# 04_-_MCU_STM32.net
KiCad netlist of a schematic drawn in Altium Designer
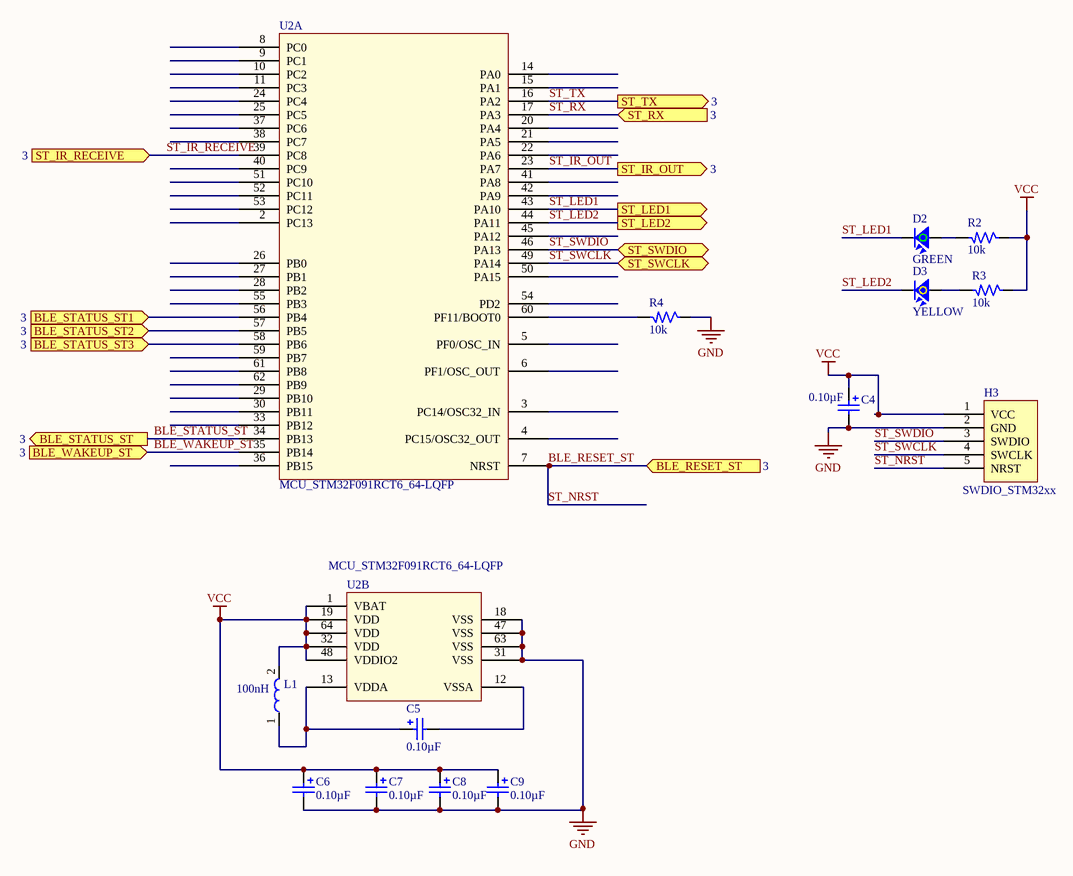
[diagram p0: [04] - MCU STM32.SchDoc]

(export (version "E")
  (design (tool "Eeschema 10.0.6"))
  (components
    (comp (ref "C4")
      (value "C_104_0603_CERAMIC_16V")
      (footprint "CAP_SMD0603")
      (description "CAP CER 0.1UF 16V X7R 0603")
      (fields
        (field (name "MANUFACTURER") "Murata Electronics North America")
        (field (name "MANUFACTURER PART NUMBER") "GRM188R71C104KA01D")
        (field (name "CAPACITANCE") "0.10µF")
      )
      (libsource (lib "ALTIUM_LIB") (part "C_104_0603_CERAMIC_16V"))
    )
    (comp (ref "C5")
      (value "C_104_0603_CERAMIC_16V")
      (footprint "CAP_SMD0603")
      (description "CAP CER 0.1UF 16V X7R 0603")
      (fields
        (field (name "MANUFACTURER") "Murata Electronics North America")
        (field (name "MANUFACTURER PART NUMBER") "GRM188R71C104KA01D")
        (field (name "CAPACITANCE") "0.10µF")
      )
      (libsource (lib "ALTIUM_LIB") (part "C_104_0603_CERAMIC_16V"))
    )
    (comp (ref "C6")
      (value "C_104_0603_CERAMIC_16V")
      (footprint "CAP_SMD0603")
      (description "CAP CER 0.1UF 16V X7R 0603")
      (fields
        (field (name "MANUFACTURER") "Murata Electronics North America")
        (field (name "MANUFACTURER PART NUMBER") "GRM188R71C104KA01D")
        (field (name "CAPACITANCE") "0.10µF")
      )
      (libsource (lib "ALTIUM_LIB") (part "C_104_0603_CERAMIC_16V"))
    )
    (comp (ref "C7")
      (value "C_104_0603_CERAMIC_16V")
      (footprint "CAP_SMD0603")
      (description "CAP CER 0.1UF 16V X7R 0603")
      (fields
        (field (name "MANUFACTURER") "Murata Electronics North America")
        (field (name "MANUFACTURER PART NUMBER") "GRM188R71C104KA01D")
        (field (name "CAPACITANCE") "0.10µF")
      )
      (libsource (lib "ALTIUM_LIB") (part "C_104_0603_CERAMIC_16V"))
    )
    (comp (ref "C8")
      (value "C_104_0603_CERAMIC_16V")
      (footprint "CAP_SMD0603")
      (description "CAP CER 0.1UF 16V X7R 0603")
      (fields
        (field (name "MANUFACTURER") "Murata Electronics North America")
        (field (name "MANUFACTURER PART NUMBER") "GRM188R71C104KA01D")
        (field (name "CAPACITANCE") "0.10µF")
      )
      (libsource (lib "ALTIUM_LIB") (part "C_104_0603_CERAMIC_16V"))
    )
    (comp (ref "C9")
      (value "C_104_0603_CERAMIC_16V")
      (footprint "CAP_SMD0603")
      (description "CAP CER 0.1UF 16V X7R 0603")
      (fields
        (field (name "MANUFACTURER") "Murata Electronics North America")
        (field (name "MANUFACTURER PART NUMBER") "GRM188R71C104KA01D")
        (field (name "CAPACITANCE") "0.10µF")
      )
      (libsource (lib "ALTIUM_LIB") (part "C_104_0603_CERAMIC_16V"))
    )
    (comp (ref "D2")
      (value "GREEN")
      (footprint "LED_GREEN_SMD0603")
      (description "LED GREEN CLEAR 0603 SMD")
      (fields
        (field (name "MANUFACTURER") "Lite-On Inc.")
        (field (name "MANUFACTURER PART NUMBER") "LTST-C191KGKT")
      )
      (libsource (lib "ALTIUM_LIB") (part "LED2_GREEN_0603_2V"))
    )
    (comp (ref "D3")
      (value "YELLOW")
      (footprint "LED_YELLOW_SMD0603")
      (description "LED YELLOW CLEAR 0603 SMD")
      (fields
        (field (name "MANUFACTURER") "Lite-On Inc.")
        (field (name "MANUFACTURER PART NUMBER") "LTST-C191KSKT")
      )
      (libsource (lib "ALTIUM_LIB") (part "LED2_YELLOW_0603_2.1V"))
    )
    (comp (ref "H3")
      (value "SWDIO_STM32xx")
      (footprint "HEADER5_ISP_STM32F0xx_SUR1.27 - duplicate")
      (description "CONN HEADER 5 POS 2.54")
      (fields
        (field (name "MANUFACTURER") "Wurth Electronics Inc")
        (field (name "MANUFACTURER PART NUMBER") "61300511121")
      )
      (libsource (lib "ALTIUM_LIB") (part "HEADER5_ISP_STM32xx_HOLE_2.54"))
    )
    (comp (ref "L1")
      (value "CHOKE_100NH_SMD0805")
      (footprint "CHOKE_SMD0805")
      (description "FIXED IND 100NH 300MA 900 MOHM")
      (fields
        (field (name "MANUFACTURER") "Jaro Components Inc.")
        (field (name "MANUFACTURER PART NUMBER") "HFI-201209-R10J")
        (field (name "INDUCTANCE") "100nH")
      )
      (libsource (lib "SchematicLib") (part "CHOKE_100NH_SMD0805"))
    )
    (comp (ref "R2")
      (value "R_10K_SMD0603_1%_1/10W")
      (footprint "RES_SMD0603")
      (description "RES SMD 10K OHM 1% 1/10W 0603")
      (fields
        (field (name "MANUFACTURER") "Yageo")
        (field (name "MANUFACTURER PART NUMBER") "RC0603FR-0710KL")
        (field (name "RESISTANCE (OHMS)") "10k")
      )
      (libsource (lib "ALTIUM_LIB") (part "R_10K_SMD0603_1%_1/10W"))
    )
    (comp (ref "R3")
      (value "R_10K_SMD0603_1%_1/10W")
      (footprint "RES_SMD0603")
      (description "RES SMD 10K OHM 1% 1/10W 0603")
      (fields
        (field (name "MANUFACTURER") "Yageo")
        (field (name "MANUFACTURER PART NUMBER") "RC0603FR-0710KL")
        (field (name "RESISTANCE (OHMS)") "10k")
      )
      (libsource (lib "ALTIUM_LIB") (part "R_10K_SMD0603_1%_1/10W"))
    )
    (comp (ref "R4")
      (value "R_10K_SMD0603_1%_1/10W")
      (footprint "RES_SMD0603")
      (description "RES SMD 10K OHM 1% 1/10W 0603")
      (fields
        (field (name "MANUFACTURER") "Yageo")
        (field (name "MANUFACTURER PART NUMBER") "RC0603FR-0710KL")
        (field (name "RESISTANCE (OHMS)") "10k")
      )
      (libsource (lib "ALTIUM_LIB") (part "R_10K_SMD0603_1%_1/10W"))
    )
    (comp (ref "U2")
      (value "MCU_STM32F091RCT6_64-LQFP")
      (footprint "MCU_STM32F091RCT6_LQFP64")
      (description "IC MCU 32BIT 256KB FLASH 64LQFP")
      (fields
        (field (name "MANUFACTURER") "STMicroelectronics")
        (field (name "MANUFACTURER PART NUMBER") "STM32F091RCT6")
      )
      (libsource (lib "ALTIUM_LIB") (part "MCU_STM32F091RCT6_64-LQFP"))
    )
  )
  (nets
    (net (code "1") (name "/BLE_RESET_ST") (class "Default")
      (node (ref "H3") (pin "5") (pinfunction "NRST_5") (pintype "passive"))
      (node (ref "U2") (pin "7") (pinfunction "NRST_7") (pintype "passive"))
    )
    (net (code "2") (name "/BLE_STATUS_ST") (class "Default")
      (node (ref "U2") (pin "34") (pinfunction "PB13_34") (pintype "passive"))
    )
    (net (code "3") (name "/BLE_STATUS_ST1") (class "Default")
      (node (ref "U2") (pin "56") (pinfunction "PB4_56") (pintype "passive"))
    )
    (net (code "4") (name "/BLE_STATUS_ST2") (class "Default")
      (node (ref "U2") (pin "57") (pinfunction "PB5_57") (pintype "passive"))
    )
    (net (code "5") (name "/BLE_STATUS_ST3") (class "Default")
      (node (ref "U2") (pin "58") (pinfunction "PB6_58") (pintype "passive"))
    )
    (net (code "6") (name "/BLE_WAKEUP_ST") (class "Default")
      (node (ref "U2") (pin "35") (pinfunction "PB14_35") (pintype "passive"))
    )
    (net (code "7") (name "/ST_IR_OUT") (class "Default")
      (node (ref "U2") (pin "23") (pinfunction "PA7_23") (pintype "passive"))
    )
    (net (code "8") (name "/ST_IR_RECEIVE") (class "Default")
      (node (ref "U2") (pin "39") (pinfunction "PC8_39") (pintype "passive"))
    )
    (net (code "9") (name "/ST_LED1") (class "Default")
      (node (ref "D2") (pin "2") (pinfunction "2_2") (pintype "passive"))
      (node (ref "U2") (pin "43") (pinfunction "PA10_43") (pintype "passive"))
    )
    (net (code "10") (name "/ST_LED2") (class "Default")
      (node (ref "D3") (pin "2") (pinfunction "2_2") (pintype "passive"))
      (node (ref "U2") (pin "44") (pinfunction "PA11_44") (pintype "passive"))
    )
    (net (code "11") (name "/ST_RX") (class "Default")
      (node (ref "U2") (pin "17") (pinfunction "PA3_17") (pintype "passive"))
    )
    (net (code "12") (name "/ST_SWCLK") (class "Default")
      (node (ref "H3") (pin "4") (pinfunction "SWCLK_4") (pintype "passive"))
      (node (ref "U2") (pin "49") (pinfunction "PA14_49") (pintype "passive"))
    )
    (net (code "13") (name "/ST_SWDIO") (class "Default")
      (node (ref "H3") (pin "3") (pinfunction "SWDIO_3") (pintype "passive"))
      (node (ref "U2") (pin "46") (pinfunction "PA13_46") (pintype "passive"))
    )
    (net (code "14") (name "/ST_TX") (class "Default")
      (node (ref "U2") (pin "16") (pinfunction "PA2_16") (pintype "passive"))
    )
    (net (code "15") (name "GND") (class "Default")
      (node (ref "C4") (pin "2") (pinfunction "2_2") (pintype "passive"))
      (node (ref "C6") (pin "2") (pinfunction "2_2") (pintype "passive"))
      (node (ref "C7") (pin "2") (pinfunction "2_2") (pintype "passive"))
      (node (ref "C8") (pin "2") (pinfunction "2_2") (pintype "passive"))
      (node (ref "C9") (pin "2") (pinfunction "2_2") (pintype "passive"))
      (node (ref "H3") (pin "2") (pinfunction "GND_2") (pintype "passive"))
      (node (ref "R4") (pin "1") (pinfunction "1_1") (pintype "passive"))
      (node (ref "U2") (pin "18") (pinfunction "VSS_18") (pintype "passive"))
      (node (ref "U2") (pin "31") (pinfunction "VSS_31") (pintype "passive"))
      (node (ref "U2") (pin "47") (pinfunction "VSS_47") (pintype "passive"))
      (node (ref "U2") (pin "63") (pinfunction "VSS_63") (pintype "passive"))
    )
    (net (code "16") (name "Net-(D2-Pad1)") (class "Default")
      (node (ref "D2") (pin "1") (pinfunction "1_1") (pintype "passive"))
      (node (ref "R2") (pin "2") (pinfunction "2_2") (pintype "passive"))
    )
    (net (code "17") (name "Net-(D3-Pad1)") (class "Default")
      (node (ref "D3") (pin "1") (pinfunction "1_1") (pintype "passive"))
      (node (ref "R3") (pin "2") (pinfunction "2_2") (pintype "passive"))
    )
    (net (code "18") (name "Net-(U2A-PF11{slash}BOOT0)") (class "Default")
      (node (ref "R4") (pin "2") (pinfunction "2_2") (pintype "passive"))
      (node (ref "U2") (pin "60") (pinfunction "PF11/BOOT0_60") (pintype "passive"))
    )
    (net (code "19") (name "Net-(U2B-VDDA)") (class "Default")
      (node (ref "C5") (pin "1") (pinfunction "1_1") (pintype "passive"))
      (node (ref "L1") (pin "1") (pinfunction "1_1") (pintype "passive"))
      (node (ref "U2") (pin "13") (pinfunction "VDDA_13") (pintype "passive"))
    )
    (net (code "20") (name "Net-(U2B-VSSA)") (class "Default")
      (node (ref "C5") (pin "2") (pinfunction "2_2") (pintype "passive"))
      (node (ref "U2") (pin "12") (pinfunction "VSSA_12") (pintype "passive"))
    )
    (net (code "21") (name "VCC") (class "Default")
      (node (ref "C4") (pin "1") (pinfunction "1_1") (pintype "passive"))
      (node (ref "C6") (pin "1") (pinfunction "1_1") (pintype "passive"))
      (node (ref "C7") (pin "1") (pinfunction "1_1") (pintype "passive"))
      (node (ref "C8") (pin "1") (pinfunction "1_1") (pintype "passive"))
      (node (ref "C9") (pin "1") (pinfunction "1_1") (pintype "passive"))
      (node (ref "H3") (pin "1") (pinfunction "VCC_1") (pintype "passive"))
      (node (ref "L1") (pin "2") (pinfunction "2_2") (pintype "passive"))
      (node (ref "R2") (pin "1") (pinfunction "1_1") (pintype "passive"))
      (node (ref "R3") (pin "1") (pinfunction "1_1") (pintype "passive"))
      (node (ref "U2") (pin "1") (pinfunction "VBAT_1") (pintype "passive"))
      (node (ref "U2") (pin "19") (pinfunction "VDD_19") (pintype "passive"))
      (node (ref "U2") (pin "32") (pinfunction "VDD_32") (pintype "passive"))
      (node (ref "U2") (pin "48") (pinfunction "VDDIO2_48") (pintype "passive"))
      (node (ref "U2") (pin "64") (pinfunction "VDD_64") (pintype "passive"))
    )
    (net (code "22") (name "unconnected-(U2A-PA0-Pad14)") (class "Default")
      (node (ref "U2") (pin "14") (pinfunction "PA0_14") (pintype "passive"))
    )
    (net (code "23") (name "unconnected-(U2A-PA1-Pad15)") (class "Default")
      (node (ref "U2") (pin "15") (pinfunction "PA1_15") (pintype "passive"))
    )
    (net (code "24") (name "unconnected-(U2A-PA4-Pad20)") (class "Default")
      (node (ref "U2") (pin "20") (pinfunction "PA4_20") (pintype "passive"))
    )
    (net (code "25") (name "unconnected-(U2A-PA5-Pad21)") (class "Default")
      (node (ref "U2") (pin "21") (pinfunction "PA5_21") (pintype "passive"))
    )
    (net (code "26") (name "unconnected-(U2A-PA6-Pad22)") (class "Default")
      (node (ref "U2") (pin "22") (pinfunction "PA6_22") (pintype "passive"))
    )
    (net (code "27") (name "unconnected-(U2A-PA8-Pad41)") (class "Default")
      (node (ref "U2") (pin "41") (pinfunction "PA8_41") (pintype "passive"))
    )
    (net (code "28") (name "unconnected-(U2A-PA9-Pad42)") (class "Default")
      (node (ref "U2") (pin "42") (pinfunction "PA9_42") (pintype "passive"))
    )
    (net (code "29") (name "unconnected-(U2A-PA12-Pad45)") (class "Default")
      (node (ref "U2") (pin "45") (pinfunction "PA12_45") (pintype "passive"))
    )
    (net (code "30") (name "unconnected-(U2A-PA15-Pad50)") (class "Default")
      (node (ref "U2") (pin "50") (pinfunction "PA15_50") (pintype "passive"))
    )
    (net (code "31") (name "unconnected-(U2A-PB0-Pad26)") (class "Default")
      (node (ref "U2") (pin "26") (pinfunction "PB0_26") (pintype "passive"))
    )
    (net (code "32") (name "unconnected-(U2A-PB1-Pad27)") (class "Default")
      (node (ref "U2") (pin "27") (pinfunction "PB1_27") (pintype "passive"))
    )
    (net (code "33") (name "unconnected-(U2A-PB2-Pad28)") (class "Default")
      (node (ref "U2") (pin "28") (pinfunction "PB2_28") (pintype "passive"))
    )
    (net (code "34") (name "unconnected-(U2A-PB3-Pad55)") (class "Default")
      (node (ref "U2") (pin "55") (pinfunction "PB3_55") (pintype "passive"))
    )
    (net (code "35") (name "unconnected-(U2A-PB7-Pad59)") (class "Default")
      (node (ref "U2") (pin "59") (pinfunction "PB7_59") (pintype "passive"))
    )
    (net (code "36") (name "unconnected-(U2A-PB8-Pad61)") (class "Default")
      (node (ref "U2") (pin "61") (pinfunction "PB8_61") (pintype "passive"))
    )
    (net (code "37") (name "unconnected-(U2A-PB9-Pad62)") (class "Default")
      (node (ref "U2") (pin "62") (pinfunction "PB9_62") (pintype "passive"))
    )
    (net (code "38") (name "unconnected-(U2A-PB10-Pad29)") (class "Default")
      (node (ref "U2") (pin "29") (pinfunction "PB10_29") (pintype "passive"))
    )
    (net (code "39") (name "unconnected-(U2A-PB11-Pad30)") (class "Default")
      (node (ref "U2") (pin "30") (pinfunction "PB11_30") (pintype "passive"))
    )
    (net (code "40") (name "unconnected-(U2A-PB12-Pad33)") (class "Default")
      (node (ref "U2") (pin "33") (pinfunction "PB12_33") (pintype "passive"))
    )
    (net (code "41") (name "unconnected-(U2A-PB15-Pad36)") (class "Default")
      (node (ref "U2") (pin "36") (pinfunction "PB15_36") (pintype "passive"))
    )
    (net (code "42") (name "unconnected-(U2A-PC0-Pad8)") (class "Default")
      (node (ref "U2") (pin "8") (pinfunction "PC0_8") (pintype "passive"))
    )
    (net (code "43") (name "unconnected-(U2A-PC1-Pad9)") (class "Default")
      (node (ref "U2") (pin "9") (pinfunction "PC1_9") (pintype "passive"))
    )
    (net (code "44") (name "unconnected-(U2A-PC2-Pad10)") (class "Default")
      (node (ref "U2") (pin "10") (pinfunction "PC2_10") (pintype "passive"))
    )
    (net (code "45") (name "unconnected-(U2A-PC3-Pad11)") (class "Default")
      (node (ref "U2") (pin "11") (pinfunction "PC3_11") (pintype "passive"))
    )
    (net (code "46") (name "unconnected-(U2A-PC4-Pad24)") (class "Default")
      (node (ref "U2") (pin "24") (pinfunction "PC4_24") (pintype "passive"))
    )
    (net (code "47") (name "unconnected-(U2A-PC5-Pad25)") (class "Default")
      (node (ref "U2") (pin "25") (pinfunction "PC5_25") (pintype "passive"))
    )
    (net (code "48") (name "unconnected-(U2A-PC6-Pad37)") (class "Default")
      (node (ref "U2") (pin "37") (pinfunction "PC6_37") (pintype "passive"))
    )
    (net (code "49") (name "unconnected-(U2A-PC7-Pad38)") (class "Default")
      (node (ref "U2") (pin "38") (pinfunction "PC7_38") (pintype "passive"))
    )
    (net (code "50") (name "unconnected-(U2A-PC9-Pad40)") (class "Default")
      (node (ref "U2") (pin "40") (pinfunction "PC9_40") (pintype "passive"))
    )
    (net (code "51") (name "unconnected-(U2A-PC10-Pad51)") (class "Default")
      (node (ref "U2") (pin "51") (pinfunction "PC10_51") (pintype "passive"))
    )
    (net (code "52") (name "unconnected-(U2A-PC11-Pad52)") (class "Default")
      (node (ref "U2") (pin "52") (pinfunction "PC11_52") (pintype "passive"))
    )
    (net (code "53") (name "unconnected-(U2A-PC12-Pad53)") (class "Default")
      (node (ref "U2") (pin "53") (pinfunction "PC12_53") (pintype "passive"))
    )
    (net (code "54") (name "unconnected-(U2A-PC13-Pad2)") (class "Default")
      (node (ref "U2") (pin "2") (pinfunction "PC13_2") (pintype "passive"))
    )
    (net (code "55") (name "unconnected-(U2A-PC14{slash}OSC32_IN-Pad3)") (class "Default")
      (node (ref "U2") (pin "3") (pinfunction "PC14/OSC32_IN_3") (pintype "passive"))
    )
    (net (code "56") (name "unconnected-(U2A-PC15{slash}OSC32_OUT-Pad4)") (class "Default")
      (node (ref "U2") (pin "4") (pinfunction "PC15/OSC32_OUT_4") (pintype "passive"))
    )
    (net (code "57") (name "unconnected-(U2A-PD2-Pad54)") (class "Default")
      (node (ref "U2") (pin "54") (pinfunction "PD2_54") (pintype "passive"))
    )
    (net (code "58") (name "unconnected-(U2A-PF0{slash}OSC_IN-Pad5)") (class "Default")
      (node (ref "U2") (pin "5") (pinfunction "PF0/OSC_IN_5") (pintype "passive"))
    )
    (net (code "59") (name "unconnected-(U2A-PF1{slash}OSC_OUT-Pad6)") (class "Default")
      (node (ref "U2") (pin "6") (pinfunction "PF1/OSC_OUT_6") (pintype "passive"))
    )
  )
)
